# 11_Miscellaneous.net
KiCad netlist of a schematic drawn in Altium Designer
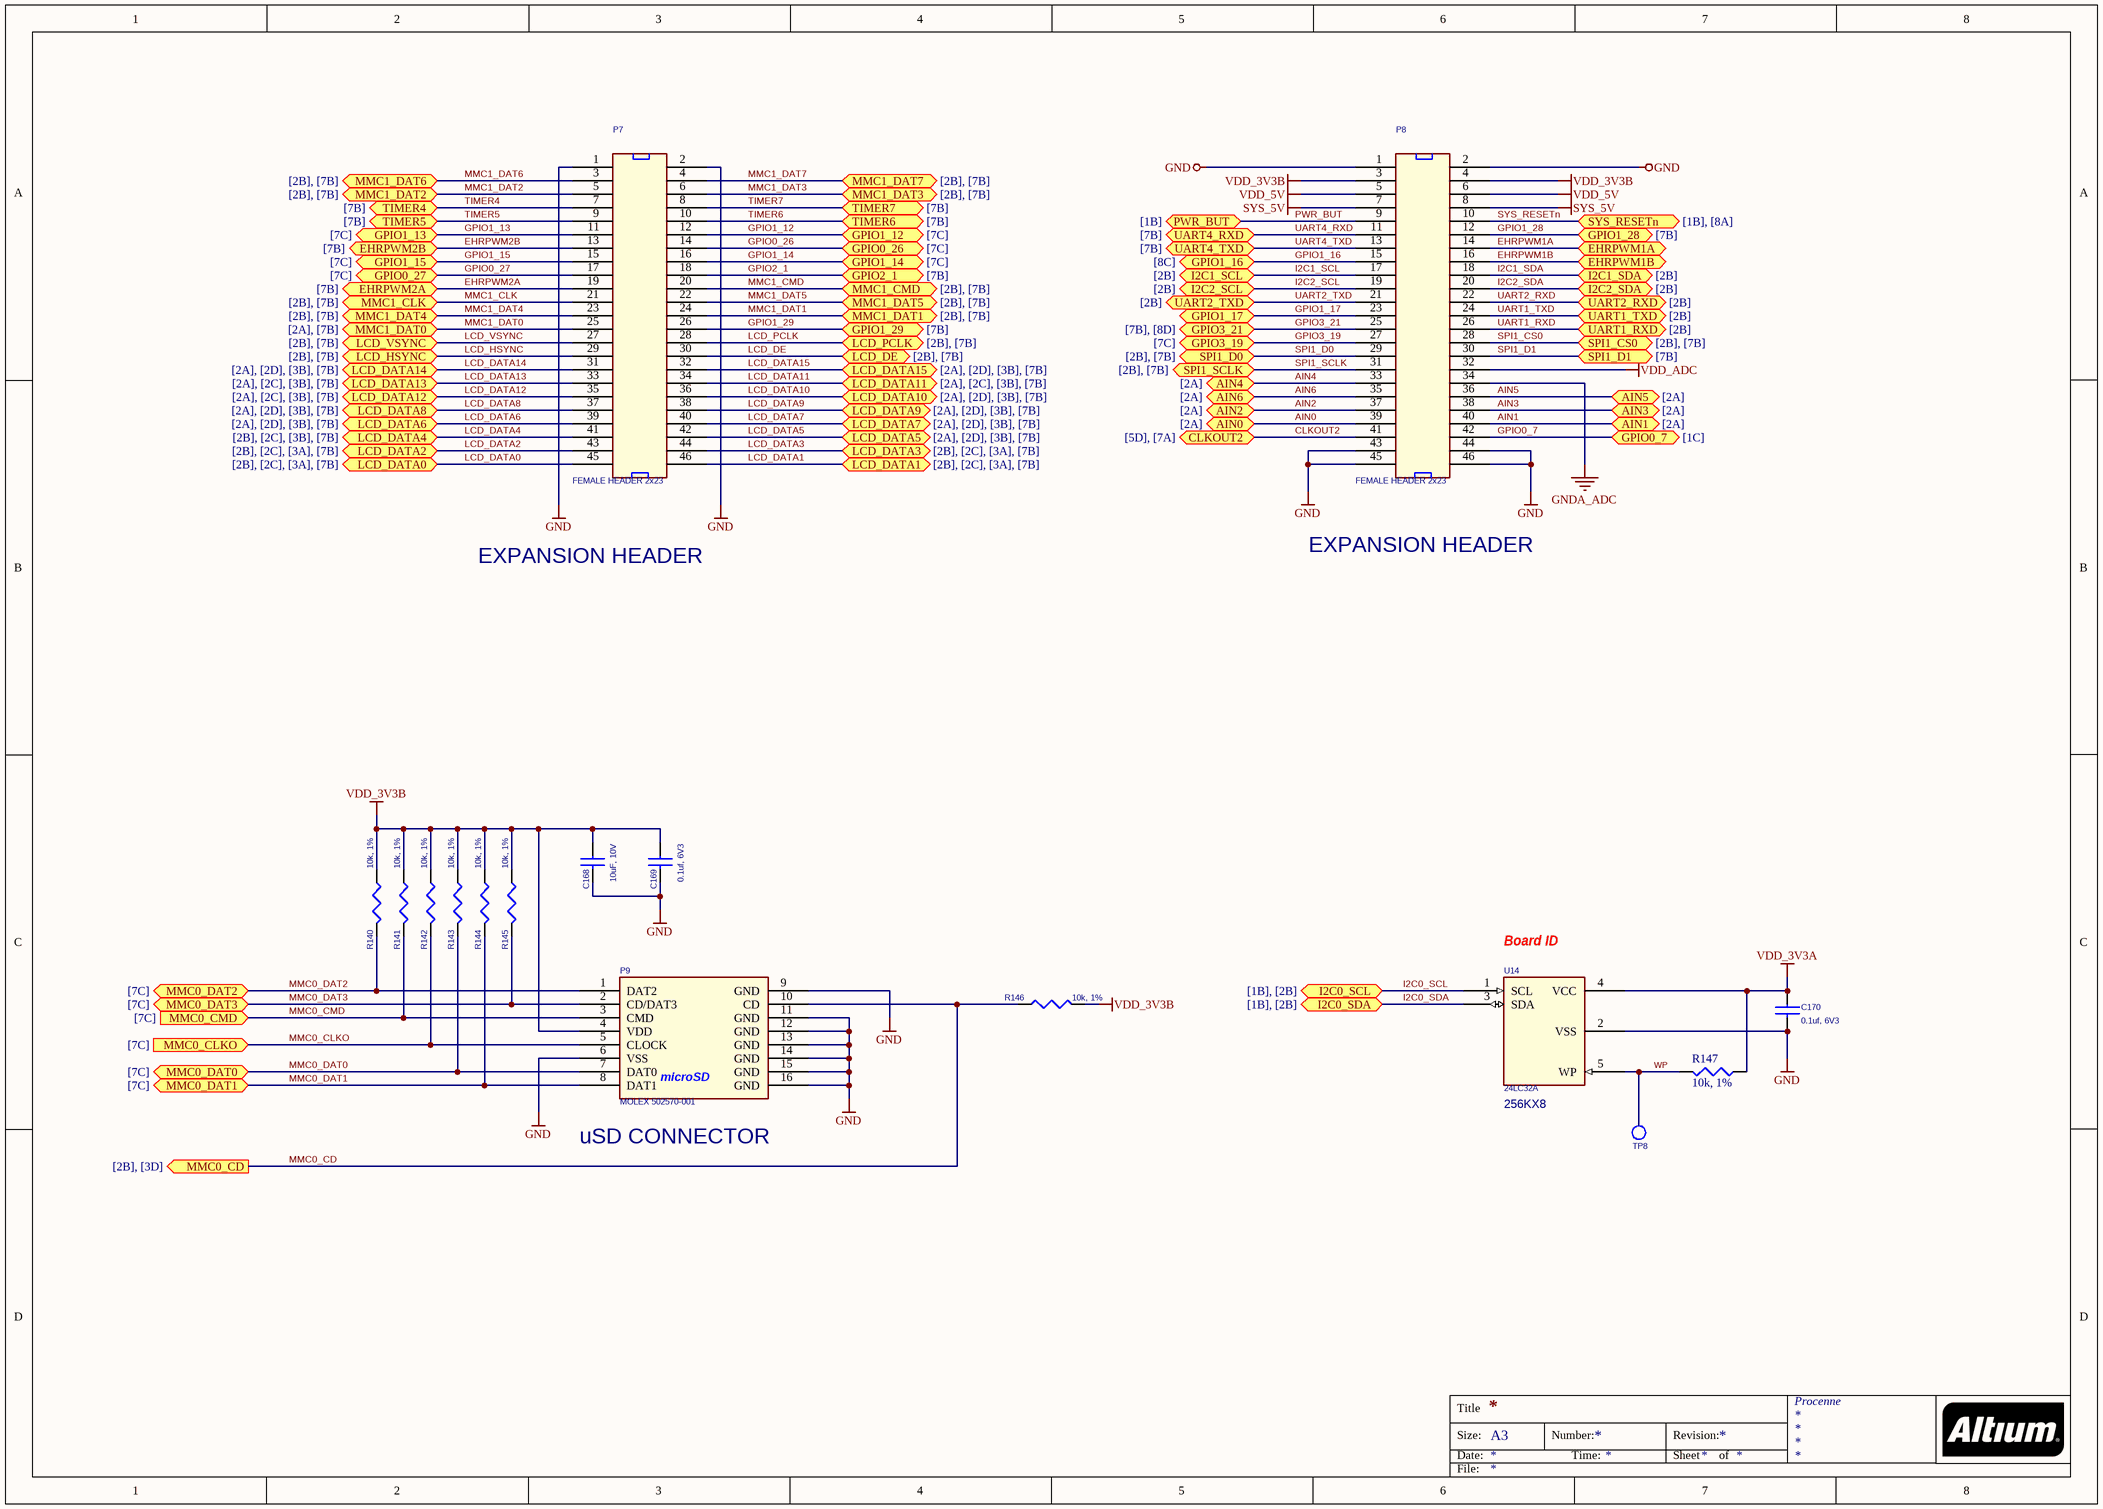
[diagram p0: 11_Miscellaneous.SchDoc]

(export (version "E")
  (design (tool "Eeschema 10.0.6"))
  (components
    (comp (ref "C168")
      (value "10uF, 10V")
      (description "CAP CER 10UF 10V Y5V 0805")
      (fields
        (field (name "MANUFACTURER") "TDK Corporation")
        (field (name "MANUFACTURER PART NUMBER") "C2012Y5V1A106Z")
      )
      (libsource (lib "BEAGLEBONEBLACK_REV A5B") (part "CAP_10uF_Y5V_10V_10%_0805"))
    )
    (comp (ref "C169")
      (value "0.1uf, 6V3")
      (footprint "402")
      (description "CAP CER 0.1UF 6.3V 10% X5R 0402")
      (fields
        (field (name "MANUFACTURER") "TDK Corporation")
        (field (name "MANUFACTURER PART NUMBER") "C1005X5R0J104K050BA")
      )
      (libsource (lib "BEAGLEBONEBLACK_REV A5B") (part "CAP_0.1uF_X7R_16V_10% 0402"))
    )
    (comp (ref "C170")
      (value "0.1uf, 6V3")
      (footprint "402")
      (description "CAP CER 0.1UF 6.3V 10% X5R 0402")
      (fields
        (field (name "MANUFACTURER") "TDK Corporation")
        (field (name "MANUFACTURER PART NUMBER") "C1005X5R0J104K050BA")
      )
      (libsource (lib "BEAGLEBONEBLACK_REV A5B") (part "CAP_0.1uF_X7R_16V_10% 0402"))
    )
    (comp (ref "P7")
      (value "FEMALE HEADER 2x23")
      (description "CONN HEADER FMAL 46PS.1\" DL GOLD")
      (fields
        (field (name "MANUFACTURER") "Sullins Connector Solutions")
        (field (name "MANUFACTURER PART NUMBER") "PPPC232LFBN-RC")
      )
      (libsource (lib "BEAGLEBONEBLACK_REV A5B") (part "HDR_46_F_2_0.1_0.1"))
    )
    (comp (ref "P8")
      (value "FEMALE HEADER 2x23")
      (description "CONN HEADER FMAL 46PS.1\" DL GOLD")
      (fields
        (field (name "MANUFACTURER") "Sullins Connector Solutions")
        (field (name "MANUFACTURER PART NUMBER") "PPPC232LFBN-RC")
      )
      (libsource (lib "BEAGLEBONEBLACK_REV A5B") (part "HDR_46_F_2_0.1_0.1"))
    )
    (comp (ref "P9")
      (value "MOLEX 502570-001")
      (footprint "SD-MICRO-SCHA5B0300")
      (description "CONN MICRO SD R/A PUSH-PUSH SMD")
      (fields
        (field (name "MANUFACTURER") "Molex Inc")
        (field (name "MANUFACTURER PART NUMBER") "5025700893")
      )
      (libsource (lib "BEAGLEBONEBLACK_REV A5B") (part "microSD_CONN_2"))
    )
    (comp (ref "R140")
      (value "10k, 1%")
      (footprint "402")
      (description "RES 10K OHM 1/16W 5% 0402 SMD")
      (fields
        (field (name "MANUFACTURER") "Rohm Semiconductor")
        (field (name "MANUFACTURER PART NUMBER") "MCR01MZPJ103")
      )
      (libsource (lib "BEAGLEBONEBLACK_REV A5B") (part "RES_10K_1/16W_1%_0402"))
    )
    (comp (ref "R141")
      (value "10k, 1%")
      (footprint "402")
      (description "RES 10K OHM 1/16W 5% 0402 SMD")
      (fields
        (field (name "MANUFACTURER") "Rohm Semiconductor")
        (field (name "MANUFACTURER PART NUMBER") "MCR01MZPJ103")
      )
      (libsource (lib "BEAGLEBONEBLACK_REV A5B") (part "RES_10K_1/16W_1%_0402"))
    )
    (comp (ref "R142")
      (value "10k, 1%")
      (footprint "402")
      (description "RES 10K OHM 1/16W 5% 0402 SMD")
      (fields
        (field (name "MANUFACTURER") "Rohm Semiconductor")
        (field (name "MANUFACTURER PART NUMBER") "MCR01MZPJ103")
      )
      (libsource (lib "BEAGLEBONEBLACK_REV A5B") (part "RES_10K_1/16W_1%_0402"))
    )
    (comp (ref "R143")
      (value "10k, 1%")
      (footprint "402")
      (description "RES 10K OHM 1/16W 5% 0402 SMD")
      (fields
        (field (name "MANUFACTURER") "Rohm Semiconductor")
        (field (name "MANUFACTURER PART NUMBER") "MCR01MZPJ103")
      )
      (libsource (lib "BEAGLEBONEBLACK_REV A5B") (part "RES_10K_1/16W_1%_0402"))
    )
    (comp (ref "R144")
      (value "10k, 1%")
      (footprint "402")
      (description "RES 10K OHM 1/16W 5% 0402 SMD")
      (fields
        (field (name "MANUFACTURER") "Rohm Semiconductor")
        (field (name "MANUFACTURER PART NUMBER") "MCR01MZPJ103")
      )
      (libsource (lib "BEAGLEBONEBLACK_REV A5B") (part "RES_10K_1/16W_1%_0402"))
    )
    (comp (ref "R145")
      (value "10k, 1%")
      (footprint "402")
      (description "RES 10K OHM 1/16W 5% 0402 SMD")
      (fields
        (field (name "MANUFACTURER") "Rohm Semiconductor")
        (field (name "MANUFACTURER PART NUMBER") "MCR01MZPJ103")
      )
      (libsource (lib "BEAGLEBONEBLACK_REV A5B") (part "RES_10K_1/16W_1%_0402"))
    )
    (comp (ref "R146")
      (value "10k, 1%")
      (footprint "402")
      (description "RES 10K OHM 1/16W 5% 0402 SMD")
      (fields
        (field (name "MANUFACTURER") "Rohm Semiconductor")
        (field (name "MANUFACTURER PART NUMBER") "MCR01MZPJ103")
      )
      (libsource (lib "BEAGLEBONEBLACK_REV A5B") (part "RES_10K_1/16W_1%_0402"))
    )
    (comp (ref "R147")
      (value "10k, 1%")
      (footprint "402")
      (description "RES 10K OHM 1/16W 5% 0402 SMD")
      (fields
        (field (name "MANUFACTURER") "Rohm Semiconductor")
        (field (name "MANUFACTURER PART NUMBER") "MCR01MZPJ103")
      )
      (libsource (lib "BEAGLEBONEBLACK_REV A5B") (part "RES_10K_1/16W_1%_0402"))
    )
    (comp (ref "TP8")
      (value "TESTPT1")
      (footprint "tp1-8040")
      (libsource (lib "BEAGLEBONEBLACK_REV A5B") (part "TESTPT1"))
    )
    (comp (ref "U14")
      (value "24LC32A")
      (footprint "SOT23-5")
      (description "IC EEPROM 32KBIT 400KHZ SOT23-5")
      (fields
        (field (name "MANUFACTURER") "Microchip Technology")
        (field (name "MANUFACTURER PART NUMBER") "24LC32AT-I/OT")
      )
      (libsource (lib "BEAGLEBONEBLACK_REV A5B") (part "24LC32A"))
    )
  )
  (nets
    (net (code "1") (name "/AIN0") (class "Default")
      (node (ref "P8") (pin "39") (pinfunction "20_39") (pintype "passive"))
    )
    (net (code "2") (name "/AIN1") (class "Default")
      (node (ref "P8") (pin "40") (pinfunction "45_40") (pintype "passive"))
    )
    (net (code "3") (name "/AIN2") (class "Default")
      (node (ref "P8") (pin "37") (pinfunction "19_37") (pintype "passive"))
    )
    (net (code "4") (name "/AIN3") (class "Default")
      (node (ref "P8") (pin "38") (pinfunction "44_38") (pintype "passive"))
    )
    (net (code "5") (name "/AIN4") (class "Default")
      (node (ref "P8") (pin "33") (pinfunction "17_33") (pintype "passive"))
    )
    (net (code "6") (name "/AIN5") (class "Default")
      (node (ref "P8") (pin "36") (pinfunction "43_36") (pintype "passive"))
    )
    (net (code "7") (name "/AIN6") (class "Default")
      (node (ref "P8") (pin "35") (pinfunction "18_35") (pintype "passive"))
    )
    (net (code "8") (name "/CLKOUT2") (class "Default")
      (node (ref "P8") (pin "41") (pinfunction "21_41") (pintype "passive"))
    )
    (net (code "9") (name "/EHRPWM1A") (class "Default")
      (node (ref "P8") (pin "14") (pinfunction "32_14") (pintype "passive"))
    )
    (net (code "10") (name "/EHRPWM1B") (class "Default")
      (node (ref "P8") (pin "16") (pinfunction "33_16") (pintype "passive"))
    )
    (net (code "11") (name "/EHRPWM2A") (class "Default")
      (node (ref "P7") (pin "19") (pinfunction "10_19") (pintype "passive"))
    )
    (net (code "12") (name "/EHRPWM2B") (class "Default")
      (node (ref "P7") (pin "13") (pinfunction "7_13") (pintype "passive"))
    )
    (net (code "13") (name "/GPIO0_7") (class "Default")
      (node (ref "P8") (pin "42") (pinfunction "46_42") (pintype "passive"))
    )
    (net (code "14") (name "/GPIO0_26") (class "Default")
      (node (ref "P7") (pin "14") (pinfunction "32_14") (pintype "passive"))
    )
    (net (code "15") (name "/GPIO0_27") (class "Default")
      (node (ref "P7") (pin "17") (pinfunction "9_17") (pintype "passive"))
    )
    (net (code "16") (name "/GPIO1_12") (class "Default")
      (node (ref "P7") (pin "12") (pinfunction "31_12") (pintype "passive"))
    )
    (net (code "17") (name "/GPIO1_13") (class "Default")
      (node (ref "P7") (pin "11") (pinfunction "6_11") (pintype "passive"))
    )
    (net (code "18") (name "/GPIO1_14") (class "Default")
      (node (ref "P7") (pin "16") (pinfunction "33_16") (pintype "passive"))
    )
    (net (code "19") (name "/GPIO1_15") (class "Default")
      (node (ref "P7") (pin "15") (pinfunction "8_15") (pintype "passive"))
    )
    (net (code "20") (name "/GPIO1_16") (class "Default")
      (node (ref "P8") (pin "15") (pinfunction "8_15") (pintype "passive"))
    )
    (net (code "21") (name "/GPIO1_17") (class "Default")
      (node (ref "P8") (pin "23") (pinfunction "12_23") (pintype "passive"))
    )
    (net (code "22") (name "/GPIO1_28") (class "Default")
      (node (ref "P8") (pin "12") (pinfunction "31_12") (pintype "passive"))
    )
    (net (code "23") (name "/GPIO1_29") (class "Default")
      (node (ref "P7") (pin "26") (pinfunction "38_26") (pintype "passive"))
    )
    (net (code "24") (name "/GPIO2_1") (class "Default")
      (node (ref "P7") (pin "18") (pinfunction "34_18") (pintype "passive"))
    )
    (net (code "25") (name "/GPIO3_19") (class "Default")
      (node (ref "P8") (pin "27") (pinfunction "14_27") (pintype "passive"))
    )
    (net (code "26") (name "/GPIO3_21") (class "Default")
      (node (ref "P8") (pin "25") (pinfunction "13_25") (pintype "passive"))
    )
    (net (code "27") (name "/I2C0_SCL") (class "Default")
      (node (ref "U14") (pin "1") (pinfunction "SCL_1") (pintype "input"))
    )
    (net (code "28") (name "/I2C0_SDA") (class "Default")
      (node (ref "U14") (pin "3") (pinfunction "SDA_3") (pintype "bidirectional"))
    )
    (net (code "29") (name "/I2C1_SCL") (class "Default")
      (node (ref "P8") (pin "17") (pinfunction "9_17") (pintype "passive"))
    )
    (net (code "30") (name "/I2C1_SDA") (class "Default")
      (node (ref "P8") (pin "18") (pinfunction "34_18") (pintype "passive"))
    )
    (net (code "31") (name "/I2C2_SCL") (class "Default")
      (node (ref "P8") (pin "19") (pinfunction "10_19") (pintype "passive"))
    )
    (net (code "32") (name "/I2C2_SDA") (class "Default")
      (node (ref "P8") (pin "20") (pinfunction "35_20") (pintype "passive"))
    )
    (net (code "33") (name "/LCD_DATA0") (class "Default")
      (node (ref "P7") (pin "45") (pinfunction "23_45") (pintype "passive"))
    )
    (net (code "34") (name "/LCD_DATA1") (class "Default")
      (node (ref "P7") (pin "46") (pinfunction "48_46") (pintype "passive"))
    )
    (net (code "35") (name "/LCD_DATA2") (class "Default")
      (node (ref "P7") (pin "43") (pinfunction "22_43") (pintype "passive"))
    )
    (net (code "36") (name "/LCD_DATA3") (class "Default")
      (node (ref "P7") (pin "44") (pinfunction "47_44") (pintype "passive"))
    )
    (net (code "37") (name "/LCD_DATA4") (class "Default")
      (node (ref "P7") (pin "41") (pinfunction "21_41") (pintype "passive"))
    )
    (net (code "38") (name "/LCD_DATA5") (class "Default")
      (node (ref "P7") (pin "42") (pinfunction "46_42") (pintype "passive"))
    )
    (net (code "39") (name "/LCD_DATA6") (class "Default")
      (node (ref "P7") (pin "39") (pinfunction "20_39") (pintype "passive"))
    )
    (net (code "40") (name "/LCD_DATA7") (class "Default")
      (node (ref "P7") (pin "40") (pinfunction "45_40") (pintype "passive"))
    )
    (net (code "41") (name "/LCD_DATA8") (class "Default")
      (node (ref "P7") (pin "37") (pinfunction "19_37") (pintype "passive"))
    )
    (net (code "42") (name "/LCD_DATA9") (class "Default")
      (node (ref "P7") (pin "38") (pinfunction "44_38") (pintype "passive"))
    )
    (net (code "43") (name "/LCD_DATA10") (class "Default")
      (node (ref "P7") (pin "36") (pinfunction "43_36") (pintype "passive"))
    )
    (net (code "44") (name "/LCD_DATA11") (class "Default")
      (node (ref "P7") (pin "34") (pinfunction "42_34") (pintype "passive"))
    )
    (net (code "45") (name "/LCD_DATA12") (class "Default")
      (node (ref "P7") (pin "35") (pinfunction "18_35") (pintype "passive"))
    )
    (net (code "46") (name "/LCD_DATA13") (class "Default")
      (node (ref "P7") (pin "33") (pinfunction "17_33") (pintype "passive"))
    )
    (net (code "47") (name "/LCD_DATA14") (class "Default")
      (node (ref "P7") (pin "31") (pinfunction "16_31") (pintype "passive"))
    )
    (net (code "48") (name "/LCD_DATA15") (class "Default")
      (node (ref "P7") (pin "32") (pinfunction "41_32") (pintype "passive"))
    )
    (net (code "49") (name "/LCD_DE") (class "Default")
      (node (ref "P7") (pin "30") (pinfunction "40_30") (pintype "passive"))
    )
    (net (code "50") (name "/LCD_HSYNC") (class "Default")
      (node (ref "P7") (pin "29") (pinfunction "15_29") (pintype "passive"))
    )
    (net (code "51") (name "/LCD_PCLK") (class "Default")
      (node (ref "P7") (pin "28") (pinfunction "39_28") (pintype "passive"))
    )
    (net (code "52") (name "/LCD_VSYNC") (class "Default")
      (node (ref "P7") (pin "27") (pinfunction "14_27") (pintype "passive"))
    )
    (net (code "53") (name "/MMC0_CD") (class "Default")
      (node (ref "P9") (pin "10") (pinfunction "CD_10") (pintype "passive"))
      (node (ref "R146") (pin "1") (pinfunction "1_1") (pintype "passive"))
    )
    (net (code "54") (name "/MMC0_CLKO") (class "Default")
      (node (ref "P9") (pin "5") (pinfunction "CLOCK_5") (pintype "passive"))
      (node (ref "R142") (pin "2") (pinfunction "2_2") (pintype "passive"))
    )
    (net (code "55") (name "/MMC0_CMD") (class "Default")
      (node (ref "P9") (pin "3") (pinfunction "CMD_3") (pintype "passive"))
      (node (ref "R141") (pin "2") (pinfunction "2_2") (pintype "passive"))
    )
    (net (code "56") (name "/MMC0_DAT0") (class "Default")
      (node (ref "P9") (pin "7") (pinfunction "DAT0_7") (pintype "passive"))
      (node (ref "R143") (pin "2") (pinfunction "2_2") (pintype "passive"))
    )
    (net (code "57") (name "/MMC0_DAT1") (class "Default")
      (node (ref "P9") (pin "8") (pinfunction "DAT1_8") (pintype "passive"))
      (node (ref "R144") (pin "2") (pinfunction "2_2") (pintype "passive"))
    )
    (net (code "58") (name "/MMC0_DAT2") (class "Default")
      (node (ref "P9") (pin "1") (pinfunction "DAT2_1") (pintype "passive"))
      (node (ref "R140") (pin "2") (pinfunction "2_2") (pintype "passive"))
    )
    (net (code "59") (name "/MMC0_DAT3") (class "Default")
      (node (ref "P9") (pin "2") (pinfunction "CD/DAT3_2") (pintype "passive"))
      (node (ref "R145") (pin "2") (pinfunction "2_2") (pintype "passive"))
    )
    (net (code "60") (name "/MMC1_CLK") (class "Default")
      (node (ref "P7") (pin "21") (pinfunction "11_21") (pintype "passive"))
    )
    (net (code "61") (name "/MMC1_CMD") (class "Default")
      (node (ref "P7") (pin "20") (pinfunction "35_20") (pintype "passive"))
    )
    (net (code "62") (name "/MMC1_DAT0") (class "Default")
      (node (ref "P7") (pin "25") (pinfunction "13_25") (pintype "passive"))
    )
    (net (code "63") (name "/MMC1_DAT1") (class "Default")
      (node (ref "P7") (pin "24") (pinfunction "37_24") (pintype "passive"))
    )
    (net (code "64") (name "/MMC1_DAT2") (class "Default")
      (node (ref "P7") (pin "5") (pinfunction "3_5") (pintype "passive"))
    )
    (net (code "65") (name "/MMC1_DAT3") (class "Default")
      (node (ref "P7") (pin "6") (pinfunction "28_6") (pintype "passive"))
    )
    (net (code "66") (name "/MMC1_DAT4") (class "Default")
      (node (ref "P7") (pin "23") (pinfunction "12_23") (pintype "passive"))
    )
    (net (code "67") (name "/MMC1_DAT5") (class "Default")
      (node (ref "P7") (pin "22") (pinfunction "36_22") (pintype "passive"))
    )
    (net (code "68") (name "/MMC1_DAT6") (class "Default")
      (node (ref "P7") (pin "3") (pinfunction "2_3") (pintype "passive"))
    )
    (net (code "69") (name "/MMC1_DAT7") (class "Default")
      (node (ref "P7") (pin "4") (pinfunction "27_4") (pintype "passive"))
    )
    (net (code "70") (name "/PWR_BUT") (class "Default")
      (node (ref "P8") (pin "9") (pinfunction "5_9") (pintype "passive"))
    )
    (net (code "71") (name "/SPI1_CS0") (class "Default")
      (node (ref "P8") (pin "28") (pinfunction "39_28") (pintype "passive"))
    )
    (net (code "72") (name "/SPI1_D0") (class "Default")
      (node (ref "P8") (pin "29") (pinfunction "15_29") (pintype "passive"))
    )
    (net (code "73") (name "/SPI1_D1") (class "Default")
      (node (ref "P8") (pin "30") (pinfunction "40_30") (pintype "passive"))
    )
    (net (code "74") (name "/SPI1_SCLK") (class "Default")
      (node (ref "P8") (pin "31") (pinfunction "16_31") (pintype "passive"))
    )
    (net (code "75") (name "/SYS_RESETn") (class "Default")
      (node (ref "P8") (pin "10") (pinfunction "30_10") (pintype "passive"))
    )
    (net (code "76") (name "/TIMER4") (class "Default")
      (node (ref "P7") (pin "7") (pinfunction "4_7") (pintype "passive"))
    )
    (net (code "77") (name "/TIMER5") (class "Default")
      (node (ref "P7") (pin "9") (pinfunction "5_9") (pintype "passive"))
    )
    (net (code "78") (name "/TIMER6") (class "Default")
      (node (ref "P7") (pin "10") (pinfunction "30_10") (pintype "passive"))
    )
    (net (code "79") (name "/TIMER7") (class "Default")
      (node (ref "P7") (pin "8") (pinfunction "29_8") (pintype "passive"))
    )
    (net (code "80") (name "/UART1_RXD") (class "Default")
      (node (ref "P8") (pin "26") (pinfunction "38_26") (pintype "passive"))
    )
    (net (code "81") (name "/UART1_TXD") (class "Default")
      (node (ref "P8") (pin "24") (pinfunction "37_24") (pintype "passive"))
    )
    (net (code "82") (name "/UART2_RXD") (class "Default")
      (node (ref "P8") (pin "22") (pinfunction "36_22") (pintype "passive"))
    )
    (net (code "83") (name "/UART2_TXD") (class "Default")
      (node (ref "P8") (pin "21") (pinfunction "11_21") (pintype "passive"))
    )
    (net (code "84") (name "/UART4_RXD") (class "Default")
      (node (ref "P8") (pin "11") (pinfunction "6_11") (pintype "passive"))
    )
    (net (code "85") (name "/UART4_TXD") (class "Default")
      (node (ref "P8") (pin "13") (pinfunction "7_13") (pintype "passive"))
    )
    (net (code "86") (name "/WP") (class "Default")
      (node (ref "R147") (pin "2") (pinfunction "2_2") (pintype "passive"))
      (node (ref "TP8") (pin "1") (pinfunction "TP_1") (pintype "passive"))
      (node (ref "U14") (pin "5") (pinfunction "WP_5") (pintype "input"))
    )
    (net (code "87") (name "GND") (class "Default")
      (node (ref "C168") (pin "2") (pinfunction "2_2") (pintype "passive"))
      (node (ref "C169") (pin "2") (pinfunction "2_2") (pintype "passive"))
      (node (ref "C170") (pin "2") (pinfunction "2_2") (pintype "passive"))
      (node (ref "P7") (pin "1") (pinfunction "1_1") (pintype "passive"))
      (node (ref "P7") (pin "2") (pinfunction "26_2") (pintype "passive"))
      (node (ref "P8") (pin "1") (pinfunction "1_1") (pintype "passive"))
      (node (ref "P8") (pin "2") (pinfunction "26_2") (pintype "passive"))
      (node (ref "P8") (pin "43") (pinfunction "22_43") (pintype "passive"))
      (node (ref "P8") (pin "44") (pinfunction "47_44") (pintype "passive"))
      (node (ref "P8") (pin "45") (pinfunction "23_45") (pintype "passive"))
      (node (ref "P8") (pin "46") (pinfunction "48_46") (pintype "passive"))
      (node (ref "P9") (pin "11") (pinfunction "GND_11") (pintype "power_in"))
      (node (ref "P9") (pin "12") (pinfunction "GND_12") (pintype "power_in"))
      (node (ref "P9") (pin "13") (pinfunction "GND_13") (pintype "passive"))
      (node (ref "P9") (pin "14") (pinfunction "GND_14") (pintype "passive"))
      (node (ref "P9") (pin "15") (pinfunction "GND_15") (pintype "passive"))
      (node (ref "P9") (pin "16") (pinfunction "GND_16") (pintype "passive"))
      (node (ref "P9") (pin "6") (pinfunction "VSS_6") (pintype "power_in"))
      (node (ref "P9") (pin "9") (pinfunction "GND_9") (pintype "power_in"))
      (node (ref "U14") (pin "2") (pinfunction "VSS_2") (pintype "power_in"))
    )
    (net (code "88") (name "GNDA_ADC") (class "Default")
      (node (ref "P8") (pin "34") (pinfunction "42_34") (pintype "passive"))
    )
    (net (code "89") (name "SYS_5V") (class "Default")
      (node (ref "P8") (pin "7") (pinfunction "4_7") (pintype "passive"))
      (node (ref "P8") (pin "8") (pinfunction "29_8") (pintype "passive"))
    )
    (net (code "90") (name "VDD_3V3A") (class "Default")
      (node (ref "C170") (pin "1") (pinfunction "1_1") (pintype "passive"))
      (node (ref "R147") (pin "1") (pinfunction "1_1") (pintype "passive"))
      (node (ref "U14") (pin "4") (pinfunction "VCC_4") (pintype "power_in"))
    )
    (net (code "91") (name "VDD_3V3B") (class "Default")
      (node (ref "C168") (pin "1") (pinfunction "1_1") (pintype "passive"))
      (node (ref "C169") (pin "1") (pinfunction "1_1") (pintype "passive"))
      (node (ref "P8") (pin "3") (pinfunction "2_3") (pintype "passive"))
      (node (ref "P8") (pin "4") (pinfunction "27_4") (pintype "passive"))
      (node (ref "P9") (pin "4") (pinfunction "VDD_4") (pintype "power_in"))
      (node (ref "R140") (pin "1") (pinfunction "1_1") (pintype "passive"))
      (node (ref "R141") (pin "1") (pinfunction "1_1") (pintype "passive"))
      (node (ref "R142") (pin "1") (pinfunction "1_1") (pintype "passive"))
      (node (ref "R143") (pin "1") (pinfunction "1_1") (pintype "passive"))
      (node (ref "R144") (pin "1") (pinfunction "1_1") (pintype "passive"))
      (node (ref "R145") (pin "1") (pinfunction "1_1") (pintype "passive"))
      (node (ref "R146") (pin "2") (pinfunction "2_2") (pintype "passive"))
    )
    (net (code "92") (name "VDD_5V") (class "Default")
      (node (ref "P8") (pin "5") (pinfunction "3_5") (pintype "passive"))
      (node (ref "P8") (pin "6") (pinfunction "28_6") (pintype "passive"))
    )
    (net (code "93") (name "VDD_ADC") (class "Default")
      (node (ref "P8") (pin "32") (pinfunction "41_32") (pintype "passive"))
    )
  )
)
